# ina125.net
KiCad netlist of a schematic drawn in EAGLE
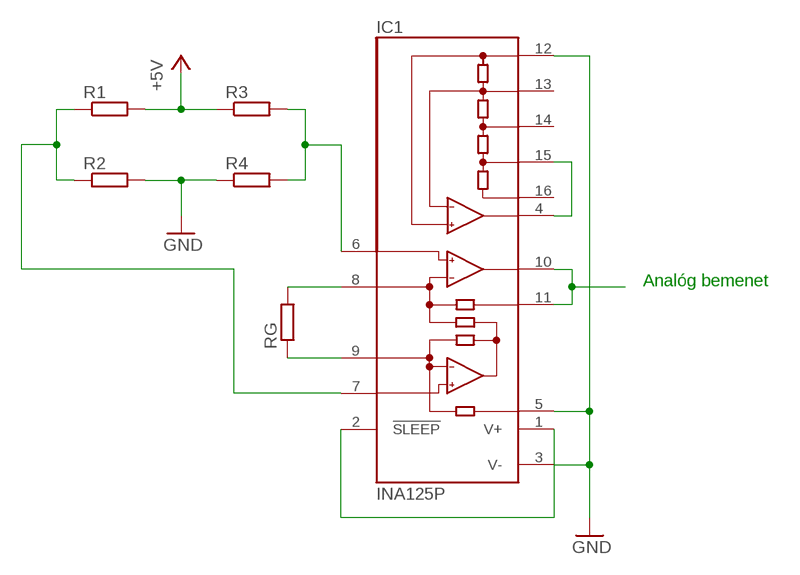
[diagram p0: schematic, sheet 1]

(export (version "E")
  (design (tool "Eeschema 10.0.6"))
  (components
    (comp (ref "IC1")
      (value "INA125P")
      (footprint "eagle-import:DIL16")
      (fields (field (name "MF") "TEXAS INSTRUMENT CONNECTORS"))
      (libsource (lib "eagle-import") (part "INA125P"))
    )
    (comp (ref "R1")
      (value "R-EU_0207/10")
      (footprint "eagle-import:0207_10")
      (libsource (lib "eagle-import") (part "R-EU_0207/10"))
    )
    (comp (ref "R2")
      (value "R-EU_0207/10")
      (footprint "eagle-import:0207_10")
      (libsource (lib "eagle-import") (part "R-EU_0207/10"))
    )
    (comp (ref "R3")
      (value "R-EU_0207/10")
      (footprint "eagle-import:0207_10")
      (libsource (lib "eagle-import") (part "R-EU_0207/10"))
    )
    (comp (ref "R4")
      (value "R-EU_0207/10")
      (footprint "eagle-import:0207_10")
      (libsource (lib "eagle-import") (part "R-EU_0207/10"))
    )
    (comp (ref "RG")
      (value "R-EU_0207/10")
      (footprint "eagle-import:0207_10")
      (libsource (lib "eagle-import") (part "R-EU_0207/10"))
    )
  )
  (nets
    (net (code "1") (name "+5V") (class "Default")
      (node (ref "R1") (pin "2") (pinfunction "2_2") (pintype "passive"))
      (node (ref "R3") (pin "1") (pinfunction "1_1") (pintype "passive"))
    )
    (net (code "2") (name "GND") (class "Default")
      (node (ref "IC1") (pin "12") (pinfunction "REFCOM_12") (pintype "passive"))
      (node (ref "IC1") (pin "3") (pinfunction "V-_3") (pintype "power_in"))
      (node (ref "IC1") (pin "5") (pinfunction "REF_5") (pintype "passive"))
      (node (ref "R2") (pin "2") (pinfunction "2_2") (pintype "passive"))
      (node (ref "R4") (pin "1") (pinfunction "1_1") (pintype "passive"))
    )
    (net (code "3") (name "Net-(IC1-+IN)") (class "Default")
      (node (ref "IC1") (pin "6") (pinfunction "+IN_6") (pintype "input"))
      (node (ref "R3") (pin "2") (pinfunction "2_2") (pintype "passive"))
      (node (ref "R4") (pin "2") (pinfunction "2_2") (pintype "passive"))
    )
    (net (code "4") (name "Net-(IC1--IN)") (class "Default")
      (node (ref "IC1") (pin "7") (pinfunction "-IN_7") (pintype "input"))
      (node (ref "R1") (pin "1") (pinfunction "1_1") (pintype "passive"))
      (node (ref "R2") (pin "1") (pinfunction "1_1") (pintype "passive"))
    )
    (net (code "5") (name "Net-(IC1-OUT)") (class "Default")
      (node (ref "IC1") (pin "10") (pinfunction "OUT_10") (pintype "output"))
      (node (ref "IC1") (pin "11") (pinfunction "SENSE_11") (pintype "passive"))
    )
    (net (code "6") (name "Net-(IC1-REF5)") (class "Default")
      (node (ref "IC1") (pin "15") (pinfunction "REF5_15") (pintype "output"))
      (node (ref "IC1") (pin "4") (pinfunction "REFOUT_4") (pintype "output"))
    )
    (net (code "7") (name "Net-(IC1-RG-Pad8)") (class "Default")
      (node (ref "IC1") (pin "8") (pinfunction "RG_8") (pintype "passive"))
      (node (ref "RG") (pin "2") (pinfunction "2_2") (pintype "passive"))
    )
    (net (code "8") (name "Net-(IC1-RG-Pad9)") (class "Default")
      (node (ref "IC1") (pin "9") (pinfunction "RG_9") (pintype "passive"))
      (node (ref "RG") (pin "1") (pinfunction "1_1") (pintype "passive"))
    )
    (net (code "9") (name "Net-(IC1-V+)") (class "Default")
      (node (ref "IC1") (pin "1") (pinfunction "V+_1") (pintype "power_in"))
      (node (ref "IC1") (pin "2") (pinfunction "~{SLEEP}_2") (pintype "input"))
    )
    (net (code "10") (name "unconnected-(IC1-REF2.5-Pad14)") (class "Default")
      (node (ref "IC1") (pin "14") (pinfunction "REF2.5_14") (pintype "output"))
    )
    (net (code "11") (name "unconnected-(IC1-REF10-Pad16)") (class "Default")
      (node (ref "IC1") (pin "16") (pinfunction "REF10_16") (pintype "output"))
    )
    (net (code "12") (name "unconnected-(IC1-REFBG-Pad13)") (class "Default")
      (node (ref "IC1") (pin "13") (pinfunction "REFBG_13") (pintype "output"))
    )
  )
)
